# Proto-BoosterPack-RevA1.net
KiCad netlist of a schematic drawn in EAGLE
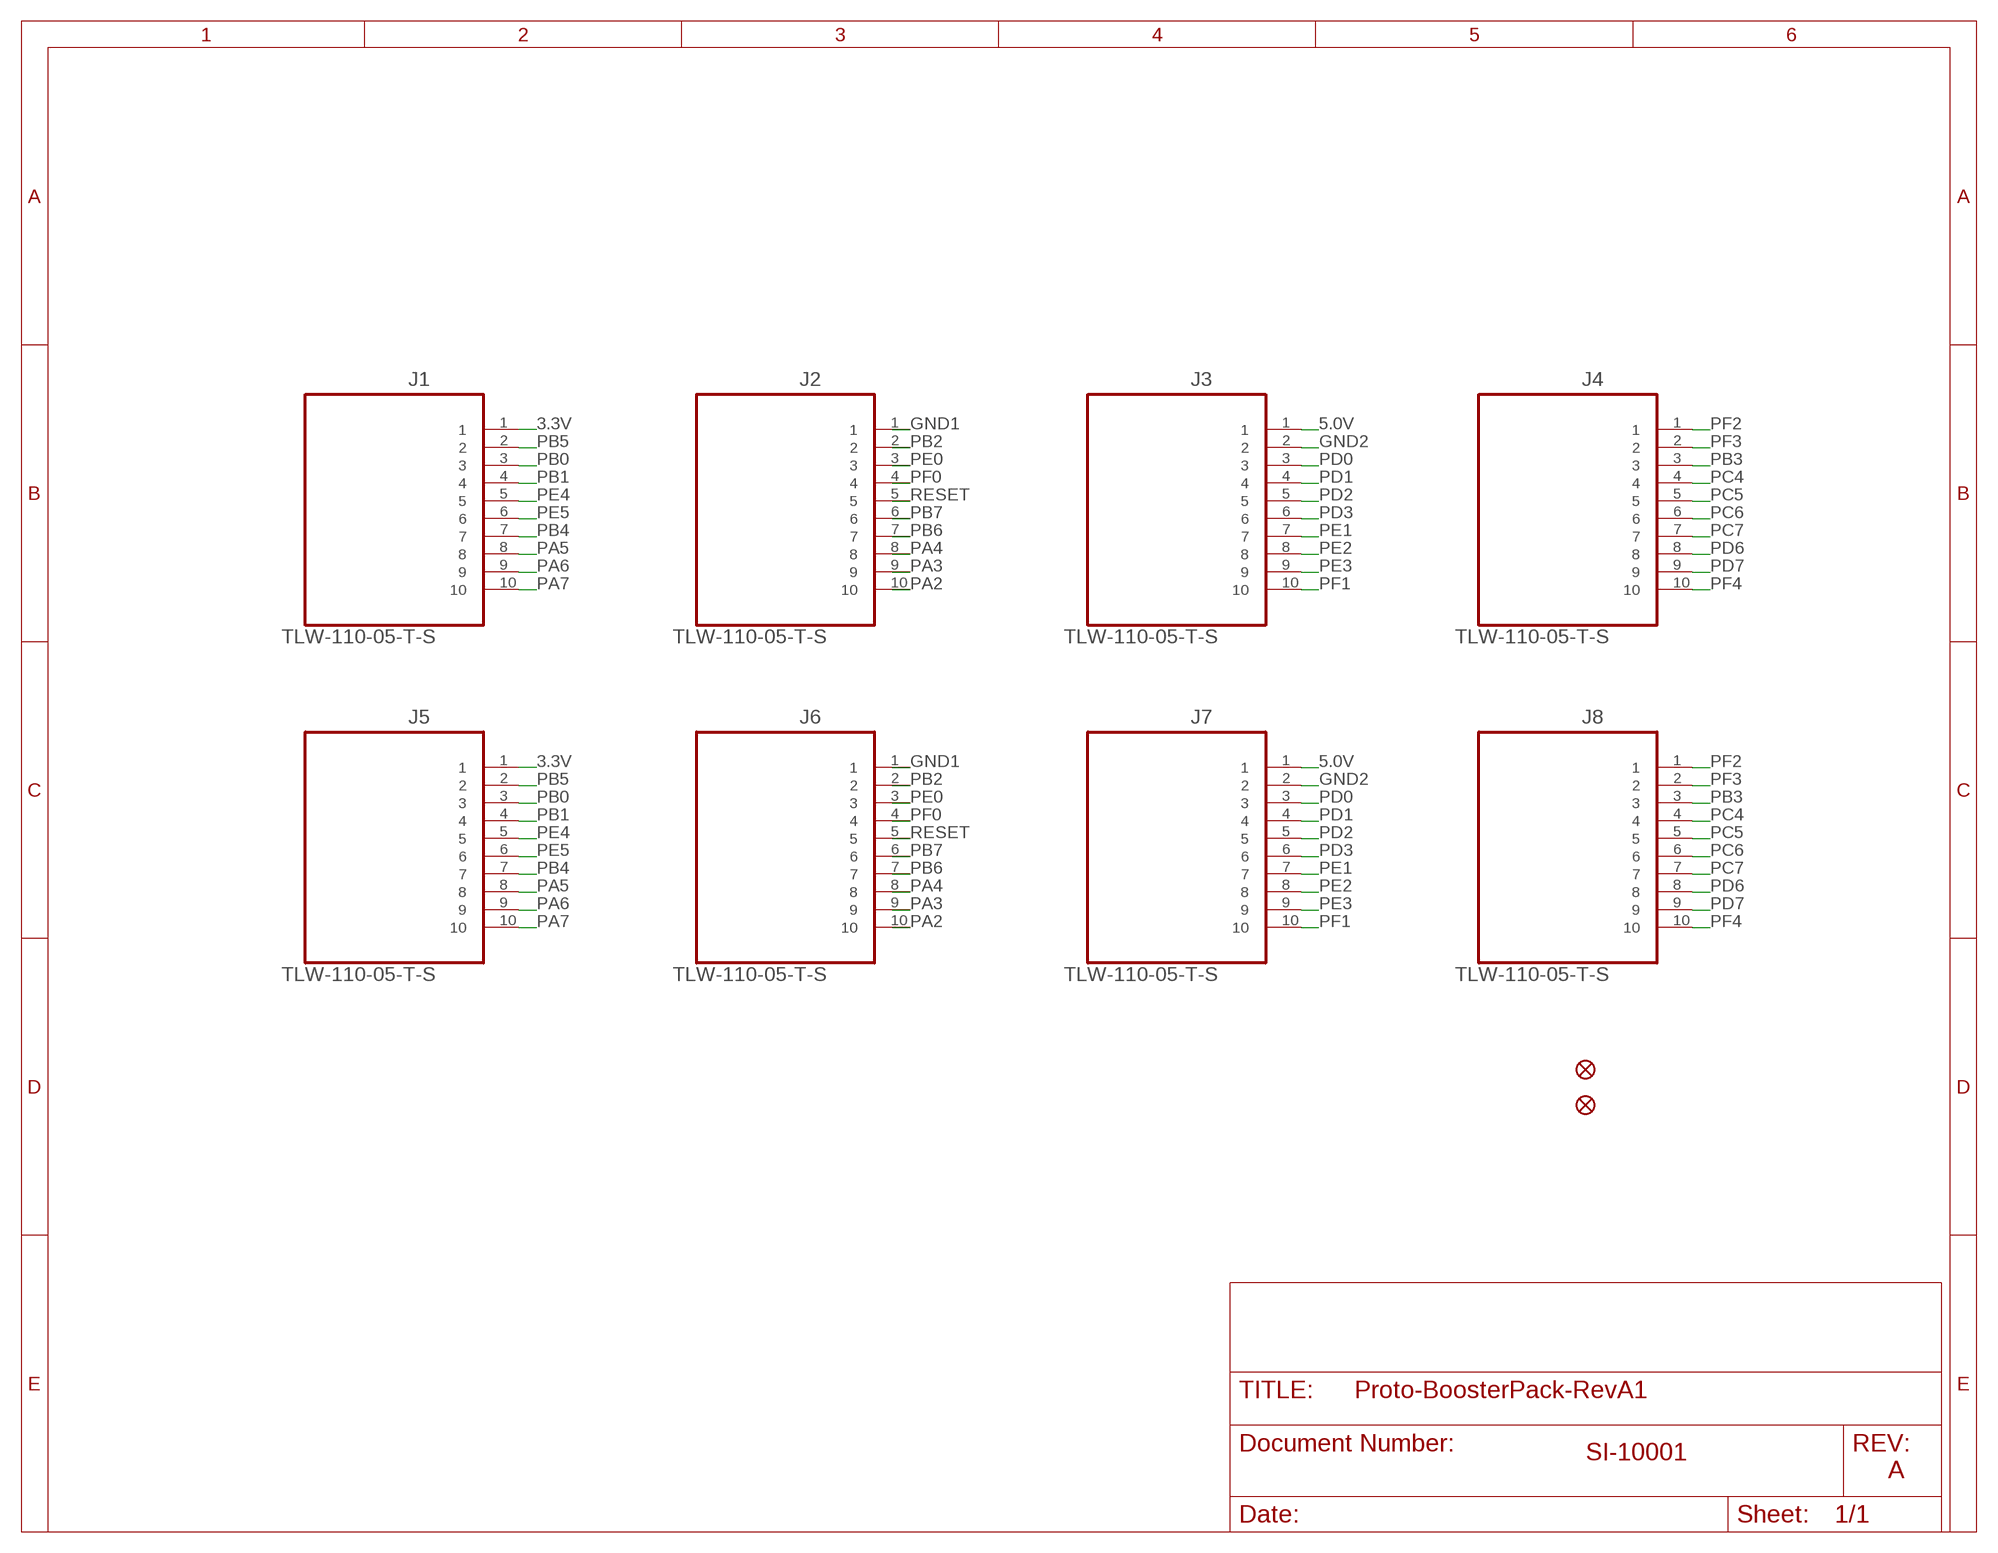
[diagram p0: schematic, sheet 1]

(export (version "E")
  (design (tool "Eeschema 10.0.6"))
  (components
    (comp (ref "FID1")
      (value "FIDUCIAL1X2")
      (footprint "eagle-import:FIDUCIAL-1X2")
      (libsource (lib "eagle-import") (part "FIDUCIAL1X2"))
    )
    (comp (ref "FID2")
      (value "FIDUCIAL1X2")
      (footprint "eagle-import:FIDUCIAL-1X2")
      (libsource (lib "eagle-import") (part "FIDUCIAL1X2"))
    )
    (comp (ref "J1")
      (value "TLW-110-05-T-S")
      (footprint "eagle-import:SAMTEC_TLW-110-05-T-S")
      (libsource (lib "eagle-import") (part "TLW-110-05-T-S"))
    )
    (comp (ref "J2")
      (value "TLW-110-05-T-S")
      (footprint "eagle-import:SAMTEC_TLW-110-05-T-S")
      (fields
        (field (name "MPN") "TLW-110-05-T-S")
        (field (name "OC_FARNELL") "-")
        (field (name "OC_NEWARK") "12P0439")
        (field (name "PACKAGE") "CONN HEADER 10 POS .100 inch")
        (field (name "SUPPLIER") "SAMTEC")
      )
      (libsource (lib "eagle-import") (part "TLW-110-05-T-S"))
    )
    (comp (ref "J3")
      (value "TLW-110-05-T-S")
      (footprint "eagle-import:SAMTEC_TLW-110-05-T-S")
      (fields
        (field (name "MPN") "TLW-110-05-T-S")
        (field (name "OC_FARNELL") "-")
        (field (name "OC_NEWARK") "12P0439")
        (field (name "PACKAGE") "CONN HEADER 10 POS .100 inch")
        (field (name "SUPPLIER") "SAMTEC")
      )
      (libsource (lib "eagle-import") (part "TLW-110-05-T-S"))
    )
    (comp (ref "J4")
      (value "TLW-110-05-T-S")
      (footprint "eagle-import:SAMTEC_TLW-110-05-T-S")
      (fields
        (field (name "MPN") "TLW-110-05-T-S")
        (field (name "OC_FARNELL") "-")
        (field (name "OC_NEWARK") "12P0439")
        (field (name "PACKAGE") "CONN HEADER 10 POS .100 inch")
        (field (name "SUPPLIER") "SAMTEC")
      )
      (libsource (lib "eagle-import") (part "TLW-110-05-T-S"))
    )
    (comp (ref "J5")
      (value "TLW-110-05-T-S")
      (footprint "eagle-import:SAMTEC_TLW-110-05-T-S")
      (libsource (lib "eagle-import") (part "TLW-110-05-T-S"))
    )
    (comp (ref "J6")
      (value "TLW-110-05-T-S")
      (footprint "eagle-import:SAMTEC_TLW-110-05-T-S")
      (fields
        (field (name "MPN") "TLW-110-05-T-S")
        (field (name "OC_FARNELL") "-")
        (field (name "OC_NEWARK") "12P0439")
        (field (name "PACKAGE") "CONN HEADER 10 POS .100 inch")
        (field (name "SUPPLIER") "SAMTEC")
      )
      (libsource (lib "eagle-import") (part "TLW-110-05-T-S"))
    )
    (comp (ref "J7")
      (value "TLW-110-05-T-S")
      (footprint "eagle-import:SAMTEC_TLW-110-05-T-S")
      (fields
        (field (name "MPN") "TLW-110-05-T-S")
        (field (name "OC_FARNELL") "-")
        (field (name "OC_NEWARK") "12P0439")
        (field (name "PACKAGE") "CONN HEADER 10 POS .100 inch")
        (field (name "SUPPLIER") "SAMTEC")
      )
      (libsource (lib "eagle-import") (part "TLW-110-05-T-S"))
    )
    (comp (ref "J8")
      (value "TLW-110-05-T-S")
      (footprint "eagle-import:SAMTEC_TLW-110-05-T-S")
      (fields
        (field (name "MPN") "TLW-110-05-T-S")
        (field (name "OC_FARNELL") "-")
        (field (name "OC_NEWARK") "12P0439")
        (field (name "PACKAGE") "CONN HEADER 10 POS .100 inch")
        (field (name "SUPPLIER") "SAMTEC")
      )
      (libsource (lib "eagle-import") (part "TLW-110-05-T-S"))
    )
  )
  (nets
    (net (code "1") (name "/3.3V") (class "Default")
      (node (ref "J1") (pin "1") (pinfunction "1_1") (pintype "passive"))
      (node (ref "J5") (pin "1") (pinfunction "1_1") (pintype "passive"))
    )
    (net (code "2") (name "/5.0V") (class "Default")
      (node (ref "J3") (pin "1") (pinfunction "1_1") (pintype "passive"))
      (node (ref "J7") (pin "1") (pinfunction "1_1") (pintype "passive"))
    )
    (net (code "3") (name "/GND1") (class "Default")
      (node (ref "J2") (pin "1") (pinfunction "1_1") (pintype "passive"))
      (node (ref "J6") (pin "1") (pinfunction "1_1") (pintype "passive"))
    )
    (net (code "4") (name "/GND2") (class "Default")
      (node (ref "J3") (pin "2") (pinfunction "2_2") (pintype "passive"))
      (node (ref "J7") (pin "2") (pinfunction "2_2") (pintype "passive"))
    )
    (net (code "5") (name "/PA2") (class "Default")
      (node (ref "J2") (pin "10") (pinfunction "10_10") (pintype "passive"))
      (node (ref "J6") (pin "10") (pinfunction "10_10") (pintype "passive"))
    )
    (net (code "6") (name "/PA3") (class "Default")
      (node (ref "J2") (pin "9") (pinfunction "9_9") (pintype "passive"))
      (node (ref "J6") (pin "9") (pinfunction "9_9") (pintype "passive"))
    )
    (net (code "7") (name "/PA4") (class "Default")
      (node (ref "J2") (pin "8") (pinfunction "8_8") (pintype "passive"))
      (node (ref "J6") (pin "8") (pinfunction "8_8") (pintype "passive"))
    )
    (net (code "8") (name "/PA5") (class "Default")
      (node (ref "J1") (pin "8") (pinfunction "8_8") (pintype "passive"))
      (node (ref "J5") (pin "8") (pinfunction "8_8") (pintype "passive"))
    )
    (net (code "9") (name "/PA6") (class "Default")
      (node (ref "J1") (pin "9") (pinfunction "9_9") (pintype "passive"))
      (node (ref "J5") (pin "9") (pinfunction "9_9") (pintype "passive"))
    )
    (net (code "10") (name "/PA7") (class "Default")
      (node (ref "J1") (pin "10") (pinfunction "10_10") (pintype "passive"))
      (node (ref "J5") (pin "10") (pinfunction "10_10") (pintype "passive"))
    )
    (net (code "11") (name "/PB0") (class "Default")
      (node (ref "J1") (pin "3") (pinfunction "3_3") (pintype "passive"))
      (node (ref "J5") (pin "3") (pinfunction "3_3") (pintype "passive"))
    )
    (net (code "12") (name "/PB1") (class "Default")
      (node (ref "J1") (pin "4") (pinfunction "4_4") (pintype "passive"))
      (node (ref "J5") (pin "4") (pinfunction "4_4") (pintype "passive"))
    )
    (net (code "13") (name "/PB2") (class "Default")
      (node (ref "J2") (pin "2") (pinfunction "2_2") (pintype "passive"))
      (node (ref "J6") (pin "2") (pinfunction "2_2") (pintype "passive"))
    )
    (net (code "14") (name "/PB3") (class "Default")
      (node (ref "J4") (pin "3") (pinfunction "3_3") (pintype "passive"))
      (node (ref "J8") (pin "3") (pinfunction "3_3") (pintype "passive"))
    )
    (net (code "15") (name "/PB4") (class "Default")
      (node (ref "J1") (pin "7") (pinfunction "7_7") (pintype "passive"))
      (node (ref "J5") (pin "7") (pinfunction "7_7") (pintype "passive"))
    )
    (net (code "16") (name "/PB5") (class "Default")
      (node (ref "J1") (pin "2") (pinfunction "2_2") (pintype "passive"))
      (node (ref "J5") (pin "2") (pinfunction "2_2") (pintype "passive"))
    )
    (net (code "17") (name "/PB6") (class "Default")
      (node (ref "J2") (pin "7") (pinfunction "7_7") (pintype "passive"))
      (node (ref "J6") (pin "7") (pinfunction "7_7") (pintype "passive"))
    )
    (net (code "18") (name "/PB7") (class "Default")
      (node (ref "J2") (pin "6") (pinfunction "6_6") (pintype "passive"))
      (node (ref "J6") (pin "6") (pinfunction "6_6") (pintype "passive"))
    )
    (net (code "19") (name "/PC4") (class "Default")
      (node (ref "J4") (pin "4") (pinfunction "4_4") (pintype "passive"))
      (node (ref "J8") (pin "4") (pinfunction "4_4") (pintype "passive"))
    )
    (net (code "20") (name "/PC5") (class "Default")
      (node (ref "J4") (pin "5") (pinfunction "5_5") (pintype "passive"))
      (node (ref "J8") (pin "5") (pinfunction "5_5") (pintype "passive"))
    )
    (net (code "21") (name "/PC6") (class "Default")
      (node (ref "J4") (pin "6") (pinfunction "6_6") (pintype "passive"))
      (node (ref "J8") (pin "6") (pinfunction "6_6") (pintype "passive"))
    )
    (net (code "22") (name "/PC7") (class "Default")
      (node (ref "J4") (pin "7") (pinfunction "7_7") (pintype "passive"))
      (node (ref "J8") (pin "7") (pinfunction "7_7") (pintype "passive"))
    )
    (net (code "23") (name "/PD0") (class "Default")
      (node (ref "J3") (pin "3") (pinfunction "3_3") (pintype "passive"))
      (node (ref "J7") (pin "3") (pinfunction "3_3") (pintype "passive"))
    )
    (net (code "24") (name "/PD1") (class "Default")
      (node (ref "J3") (pin "4") (pinfunction "4_4") (pintype "passive"))
      (node (ref "J7") (pin "4") (pinfunction "4_4") (pintype "passive"))
    )
    (net (code "25") (name "/PD2") (class "Default")
      (node (ref "J3") (pin "5") (pinfunction "5_5") (pintype "passive"))
      (node (ref "J7") (pin "5") (pinfunction "5_5") (pintype "passive"))
    )
    (net (code "26") (name "/PD3") (class "Default")
      (node (ref "J3") (pin "6") (pinfunction "6_6") (pintype "passive"))
      (node (ref "J7") (pin "6") (pinfunction "6_6") (pintype "passive"))
    )
    (net (code "27") (name "/PD6") (class "Default")
      (node (ref "J4") (pin "8") (pinfunction "8_8") (pintype "passive"))
      (node (ref "J8") (pin "8") (pinfunction "8_8") (pintype "passive"))
    )
    (net (code "28") (name "/PD7") (class "Default")
      (node (ref "J4") (pin "9") (pinfunction "9_9") (pintype "passive"))
      (node (ref "J8") (pin "9") (pinfunction "9_9") (pintype "passive"))
    )
    (net (code "29") (name "/PE0") (class "Default")
      (node (ref "J2") (pin "3") (pinfunction "3_3") (pintype "passive"))
      (node (ref "J6") (pin "3") (pinfunction "3_3") (pintype "passive"))
    )
    (net (code "30") (name "/PE1") (class "Default")
      (node (ref "J3") (pin "7") (pinfunction "7_7") (pintype "passive"))
      (node (ref "J7") (pin "7") (pinfunction "7_7") (pintype "passive"))
    )
    (net (code "31") (name "/PE2") (class "Default")
      (node (ref "J3") (pin "8") (pinfunction "8_8") (pintype "passive"))
      (node (ref "J7") (pin "8") (pinfunction "8_8") (pintype "passive"))
    )
    (net (code "32") (name "/PE3") (class "Default")
      (node (ref "J3") (pin "9") (pinfunction "9_9") (pintype "passive"))
      (node (ref "J7") (pin "9") (pinfunction "9_9") (pintype "passive"))
    )
    (net (code "33") (name "/PE4") (class "Default")
      (node (ref "J1") (pin "5") (pinfunction "5_5") (pintype "passive"))
      (node (ref "J5") (pin "5") (pinfunction "5_5") (pintype "passive"))
    )
    (net (code "34") (name "/PE5") (class "Default")
      (node (ref "J1") (pin "6") (pinfunction "6_6") (pintype "passive"))
      (node (ref "J5") (pin "6") (pinfunction "6_6") (pintype "passive"))
    )
    (net (code "35") (name "/PF0") (class "Default")
      (node (ref "J2") (pin "4") (pinfunction "4_4") (pintype "passive"))
      (node (ref "J6") (pin "4") (pinfunction "4_4") (pintype "passive"))
    )
    (net (code "36") (name "/PF1") (class "Default")
      (node (ref "J3") (pin "10") (pinfunction "10_10") (pintype "passive"))
      (node (ref "J7") (pin "10") (pinfunction "10_10") (pintype "passive"))
    )
    (net (code "37") (name "/PF2") (class "Default")
      (node (ref "J4") (pin "1") (pinfunction "1_1") (pintype "passive"))
      (node (ref "J8") (pin "1") (pinfunction "1_1") (pintype "passive"))
    )
    (net (code "38") (name "/PF3") (class "Default")
      (node (ref "J4") (pin "2") (pinfunction "2_2") (pintype "passive"))
      (node (ref "J8") (pin "2") (pinfunction "2_2") (pintype "passive"))
    )
    (net (code "39") (name "/PF4") (class "Default")
      (node (ref "J4") (pin "10") (pinfunction "10_10") (pintype "passive"))
      (node (ref "J8") (pin "10") (pinfunction "10_10") (pintype "passive"))
    )
    (net (code "40") (name "/RESET") (class "Default")
      (node (ref "J2") (pin "5") (pinfunction "5_5") (pintype "passive"))
      (node (ref "J6") (pin "5") (pinfunction "5_5") (pintype "passive"))
    )
  )
)
